# 555.net
KiCad netlist of a schematic drawn in Altium Designer
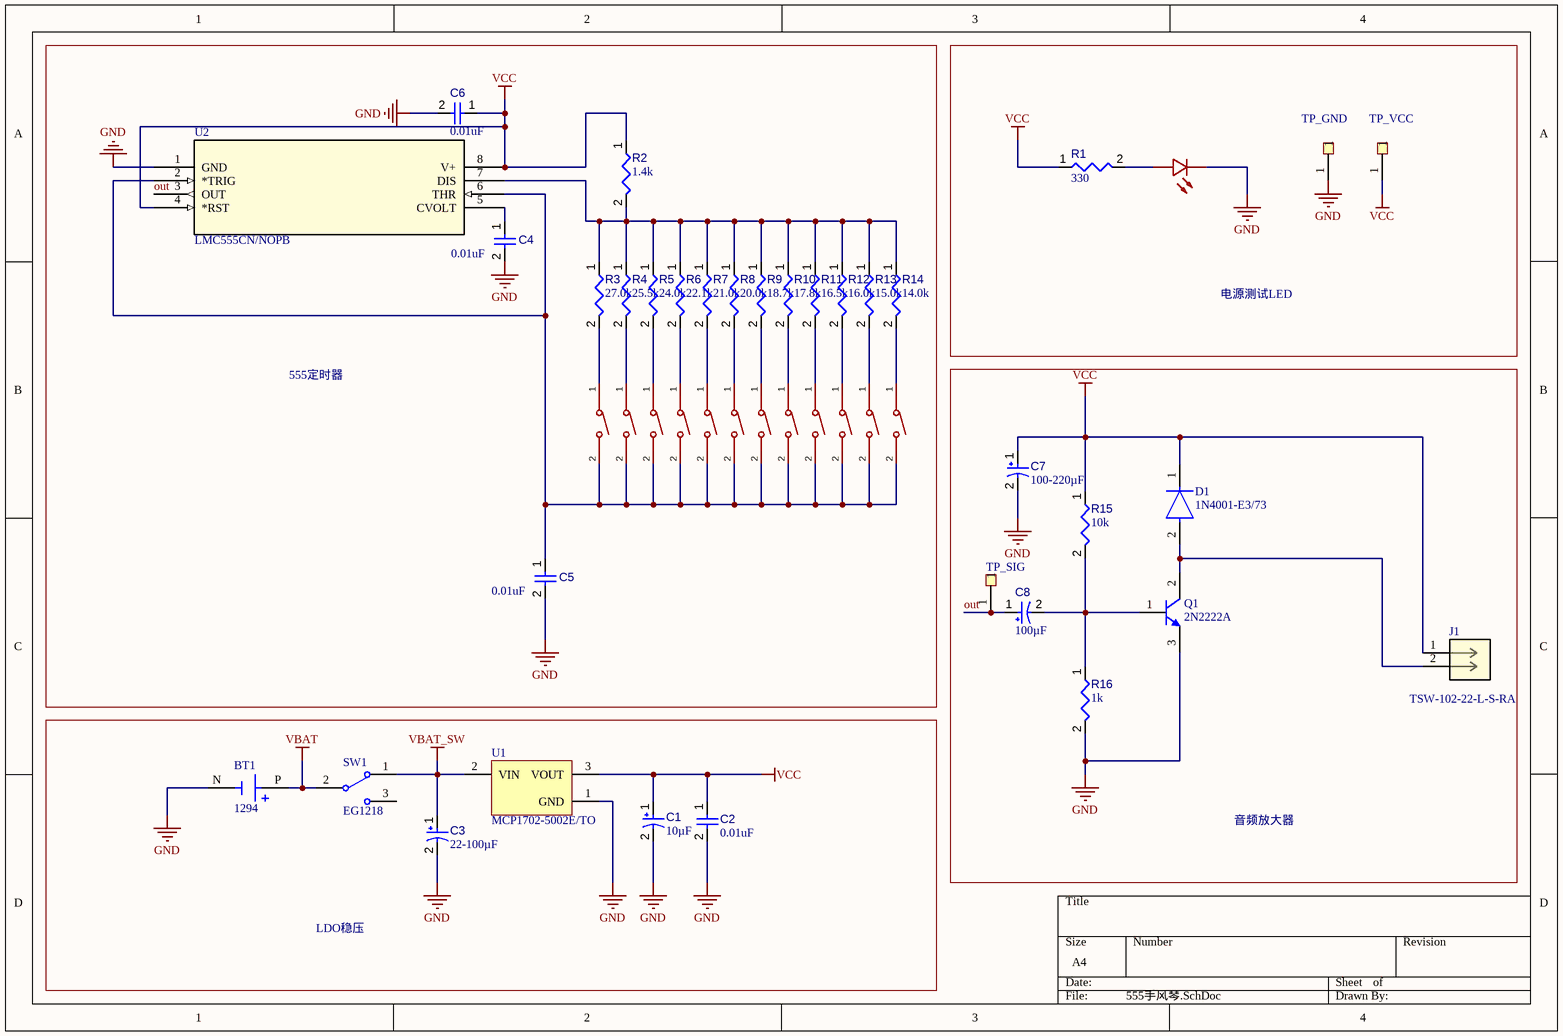
[diagram p0: 555手风琴.SchDoc]

(export (version "E")
  (design (tool "Eeschema 10.0.6"))
  (components
    (comp (ref "BT1")
      (value "1294")
      (footprint "BAT_1294")
      (description "9 Volt Battery Holder- PC Terminals")
      (fields (field (name "MF") "Keystone Electronics"))
      (libsource (lib "keystone1294电池底座") (part "1294"))
    )
    (comp (ref "C1")
      (value "10µF")
      (footprint "CAPMP3217X18-T_V")
      (description "Standard Tantalum, 10 uF, +/- 10%, 16 V, -55 to 125 degC, 1206 (3216 Metric), RoHS, Tape and Reel")
      (fields (field (name "TOLERANCE") "10%") (field (name "MANUFACTURER") "AVX"))
      (libsource (lib "") (part "CAP-P-2_1"))
    )
    (comp (ref "C2")
      (value "0.01uF")
      (footprint "CAPC2013X95X50LL10T25")
      (description "Chip Capacitor, 100 nF, +/- 10%, 50 V, 0805 (2012 Metric)")
      (fields (field (name "TOLERANCE") "10%") (field (name "Comment") "Capacitor 100 nF +/-10% 50 V 0805"))
      (libsource (lib "新宇 付") (part "CAP-NP-2"))
    )
    (comp (ref "C3")
      (value "22-100µF")
      (footprint "CAPMP3217X18-T_V")
      (description "Standard Tantalum, 10 uF, +/- 10%, 16 V, -55 to 125 degC, 1206 (3216 Metric), RoHS, Tape and Reel")
      (fields (field (name "TOLERANCE") "10%") (field (name "MANUFACTURER") "AVX"))
      (libsource (lib "") (part "CAP-P-2_1"))
    )
    (comp (ref "C4")
      (value "0.01uF")
      (footprint "CAPC2013X95X50LL10T25")
      (description "Chip Capacitor, 100 nF, +/- 10%, 50 V, 0805 (2012 Metric)")
      (fields (field (name "TOLERANCE") "10%") (field (name "Comment") "Capacitor 100 nF +/-10% 50 V 0805"))
      (libsource (lib "新宇 付") (part "CAP-NP-2"))
    )
    (comp (ref "C5")
      (value "0.01uF")
      (footprint "CAPC2013X95X50LL10T25")
      (description "Chip Capacitor, 100 nF, +/- 10%, 50 V, 0805 (2012 Metric)")
      (fields (field (name "TOLERANCE") "10%") (field (name "Comment") "Capacitor 100 nF +/-10% 50 V 0805"))
      (libsource (lib "新宇 付") (part "CAP-NP-2"))
    )
    (comp (ref "C6")
      (value "0.01uF")
      (footprint "CAPC2013X95X50LL10T25")
      (description "Chip Capacitor, 100 nF, +/- 10%, 50 V, 0805 (2012 Metric)")
      (fields (field (name "TOLERANCE") "10%") (field (name "Comment") "Capacitor 100 nF +/-10% 50 V 0805"))
      (libsource (lib "新宇 付") (part "CAP-NP-2"))
    )
    (comp (ref "C7")
      (value "100-220µF")
      (footprint "CAPMP3217X18-T_V")
      (description "Standard Tantalum, 10 uF, +/- 10%, 16 V, -55 to 125 degC, 1206 (3216 Metric), RoHS, Tape and Reel")
      (fields (field (name "TOLERANCE") "10%") (field (name "MANUFACTURER") "AVX"))
      (libsource (lib "") (part "CAP-P-2_1"))
    )
    (comp (ref "C8")
      (value "100µF")
      (footprint "CAPMP3217X18-T_V")
      (description "Standard Tantalum, 10 uF, +/- 10%, 16 V, -55 to 125 degC, 1206 (3216 Metric), RoHS, Tape and Reel")
      (fields (field (name "TOLERANCE") "10%") (field (name "MANUFACTURER") "AVX"))
      (libsource (lib "新宇 付") (part "CAP-P-2"))
    )
    (comp (ref "D1")
      (value "1N4001-E3/73")
      (footprint "FP-1N4001-E3-73-MFG")
      (description "DIODE GEN PURP 50V 1A DO204AL")
      (fields
        (field (name "MANUFACTURER") "Vishay")
        (field (name "OCTOPART") "https://octopart.com/1n4001-e3%2F73-vishay-42330130")
      )
      (libsource (lib "Altium Content Vault") (part "d7152d700b627762746794eb795d46e"))
    )
    (comp (ref "J1")
      (value "TSW-102-22-L-S-RA")
      (footprint "CON2_1X2_TR_TSW_SAI")
      (description "No Description Available")
      (fields (field (name "COPYRIGHT") "Copyright (C) 2026 Ultra Librarian. All rights reserved."))
      (libsource (lib "TSW-102-22-L-S-RA") (part "TSW-102-22-L-S-RA"))
    )
    (comp (ref "LED1")
      (value "FC-DA1608HRK-620D")
      (footprint "LED0603-RD_RED")
      (libsource (lib "C84263_发光二极管-LED_0603") (part "FC-DA1608HRK-620D"))
    )
    (comp (ref "Q1")
      (value "2N2222A")
      (footprint "STM-TO-18-3")
      (description "High Speed Switch, 0.6 A IC, -65 to 175 degC, 3-Pin TO-18, RoHS, Bulk")
      (fields (field (name "MANUFACTURER") "STMicroelectronics"))
      (libsource (lib "Altium Content Vault") (part "NPN_B1C2E3-3"))
    )
    (comp (ref "R1")
      (value "330")
      (footprint "RESC0402(1005)_L")
      (description "100R 0.063W 1% 0402 (1005 Metric)  SMD")
      (fields (field (name "TOLERANCE") "1%") (field (name "POWER") "63mW"))
      (libsource (lib "新宇 付") (part "100R2F"))
    )
    (comp (ref "R2")
      (value "1.4k")
      (footprint "RESC0402(1005)_L")
      (description "100R 0.063W 1% 0402 (1005 Metric)  SMD")
      (fields (field (name "TOLERANCE") "1%") (field (name "POWER") "63mW"))
      (libsource (lib "新宇 付") (part "100R2F"))
    )
    (comp (ref "R3")
      (value "27.0k")
      (footprint "RESC0402(1005)_L")
      (description "100R 0.063W 1% 0402 (1005 Metric)  SMD")
      (fields (field (name "TOLERANCE") "1%") (field (name "POWER") "63mW"))
      (libsource (lib "新宇 付") (part "100R2F"))
    )
    (comp (ref "R4")
      (value "25.5k")
      (footprint "RESC0402(1005)_L")
      (description "100R 0.063W 1% 0402 (1005 Metric)  SMD")
      (fields (field (name "TOLERANCE") "1%") (field (name "POWER") "63mW"))
      (libsource (lib "新宇 付") (part "100R2F"))
    )
    (comp (ref "R5")
      (value "24.0k")
      (footprint "RESC0402(1005)_L")
      (description "100R 0.063W 1% 0402 (1005 Metric)  SMD")
      (fields (field (name "TOLERANCE") "1%") (field (name "POWER") "63mW"))
      (libsource (lib "新宇 付") (part "100R2F"))
    )
    (comp (ref "R6")
      (value "22.1k")
      (footprint "RESC0402(1005)_L")
      (description "100R 0.063W 1% 0402 (1005 Metric)  SMD")
      (fields (field (name "TOLERANCE") "1%") (field (name "POWER") "63mW"))
      (libsource (lib "新宇 付") (part "100R2F"))
    )
    (comp (ref "R7")
      (value "21.0k")
      (footprint "RESC0402(1005)_L")
      (description "100R 0.063W 1% 0402 (1005 Metric)  SMD")
      (fields (field (name "TOLERANCE") "1%") (field (name "POWER") "63mW"))
      (libsource (lib "新宇 付") (part "100R2F"))
    )
    (comp (ref "R8")
      (value "20.0k")
      (footprint "RESC0402(1005)_L")
      (description "100R 0.063W 1% 0402 (1005 Metric)  SMD")
      (fields (field (name "TOLERANCE") "1%") (field (name "POWER") "63mW"))
      (libsource (lib "新宇 付") (part "100R2F"))
    )
    (comp (ref "R9")
      (value "18.7k")
      (footprint "RESC0402(1005)_L")
      (description "100R 0.063W 1% 0402 (1005 Metric)  SMD")
      (fields (field (name "TOLERANCE") "1%") (field (name "POWER") "63mW"))
      (libsource (lib "新宇 付") (part "100R2F"))
    )
    (comp (ref "R10")
      (value "17.8k")
      (footprint "RESC0402(1005)_L")
      (description "100R 0.063W 1% 0402 (1005 Metric)  SMD")
      (fields (field (name "TOLERANCE") "1%") (field (name "POWER") "63mW"))
      (libsource (lib "新宇 付") (part "100R2F"))
    )
    (comp (ref "R11")
      (value "16.5k")
      (footprint "RESC0402(1005)_L")
      (description "100R 0.063W 1% 0402 (1005 Metric)  SMD")
      (fields (field (name "TOLERANCE") "1%") (field (name "POWER") "63mW"))
      (libsource (lib "新宇 付") (part "100R2F"))
    )
    (comp (ref "R12")
      (value "16.0k")
      (footprint "RESC0402(1005)_L")
      (description "100R 0.063W 1% 0402 (1005 Metric)  SMD")
      (fields (field (name "TOLERANCE") "1%") (field (name "POWER") "63mW"))
      (libsource (lib "新宇 付") (part "100R2F"))
    )
    (comp (ref "R13")
      (value "15.0k")
      (footprint "RESC0402(1005)_L")
      (description "100R 0.063W 1% 0402 (1005 Metric)  SMD")
      (fields (field (name "TOLERANCE") "1%") (field (name "POWER") "63mW"))
      (libsource (lib "新宇 付") (part "100R2F"))
    )
    (comp (ref "R14")
      (value "14.0k")
      (footprint "RESC0402(1005)_L")
      (description "100R 0.063W 1% 0402 (1005 Metric)  SMD")
      (fields (field (name "TOLERANCE") "1%") (field (name "POWER") "63mW"))
      (libsource (lib "新宇 付") (part "100R2F"))
    )
    (comp (ref "R15")
      (value "10k")
      (footprint "RESC0402(1005)_L")
      (description "100R 0.063W 1% 0402 (1005 Metric)  SMD")
      (fields (field (name "TOLERANCE") "1%") (field (name "POWER") "63mW"))
      (libsource (lib "新宇 付") (part "100R2F"))
    )
    (comp (ref "R16")
      (value "1k")
      (footprint "RESC0402(1005)_L")
      (description "100R 0.063W 1% 0402 (1005 Metric)  SMD")
      (fields (field (name "TOLERANCE") "1%") (field (name "POWER") "63mW"))
      (libsource (lib "新宇 付") (part "100R2F"))
    )
    (comp (ref "SW1")
      (value "EG1218")
      (footprint "ESWI-EG1218_V")
      (description "Slide Switch, 500 V, -20 to 70 degC, 3-Pin THD, RoHS")
      (libsource (lib "EG1218单刀双掷滑动开关") (part "CMP-1696-00002-1"))
    )
    (comp (ref "SW2")
      (value "TS-1088-AR02016")
      (footprint "SW-SMD_L3.9-W3.0-P4.45")
      (libsource (lib "Click_switch") (part "TS-1088-AR02016"))
    )
    (comp (ref "SW3")
      (value "TS-1088-AR02016")
      (footprint "SW-SMD_L3.9-W3.0-P4.45")
      (libsource (lib "Click_switch") (part "TS-1088-AR02016"))
    )
    (comp (ref "SW4")
      (value "TS-1088-AR02016")
      (footprint "SW-SMD_L3.9-W3.0-P4.45")
      (libsource (lib "Click_switch") (part "TS-1088-AR02016"))
    )
    (comp (ref "SW5")
      (value "TS-1088-AR02016")
      (footprint "SW-SMD_L3.9-W3.0-P4.45")
      (libsource (lib "Click_switch") (part "TS-1088-AR02016"))
    )
    (comp (ref "SW6")
      (value "TS-1088-AR02016")
      (footprint "SW-SMD_L3.9-W3.0-P4.45")
      (libsource (lib "Click_switch") (part "TS-1088-AR02016"))
    )
    (comp (ref "SW7")
      (value "TS-1088-AR02016")
      (footprint "SW-SMD_L3.9-W3.0-P4.45")
      (libsource (lib "Click_switch") (part "TS-1088-AR02016"))
    )
    (comp (ref "SW8")
      (value "TS-1088-AR02016")
      (footprint "SW-SMD_L3.9-W3.0-P4.45")
      (libsource (lib "Click_switch") (part "TS-1088-AR02016"))
    )
    (comp (ref "SW9")
      (value "TS-1088-AR02016")
      (footprint "SW-SMD_L3.9-W3.0-P4.45")
      (libsource (lib "Click_switch") (part "TS-1088-AR02016"))
    )
    (comp (ref "SW10")
      (value "TS-1088-AR02016")
      (footprint "SW-SMD_L3.9-W3.0-P4.45")
      (libsource (lib "Click_switch") (part "TS-1088-AR02016"))
    )
    (comp (ref "SW11")
      (value "TS-1088-AR02016")
      (footprint "SW-SMD_L3.9-W3.0-P4.45")
      (libsource (lib "Click_switch") (part "TS-1088-AR02016"))
    )
    (comp (ref "SW12")
      (value "TS-1088-AR02016")
      (footprint "SW-SMD_L3.9-W3.0-P4.45")
      (libsource (lib "Click_switch") (part "TS-1088-AR02016"))
    )
    (comp (ref "SW13")
      (value "TS-1088-AR02016")
      (footprint "SW-SMD_L3.9-W3.0-P4.45")
      (libsource (lib "Click_switch") (part "TS-1088-AR02016"))
    )
    (comp (ref "TP_GND")
      (value "Component_1")
      (footprint "PCBComponent_1")
      (libsource (lib "testpoint") (part "Component_1"))
    )
    (comp (ref "TP_SIG")
      (value "Component_1")
      (footprint "PCBComponent_1")
      (libsource (lib "testpoint") (part "Component_1"))
    )
    (comp (ref "TP_VCC")
      (value "Component_1")
      (footprint "PCBComponent_1")
      (libsource (lib "testpoint") (part "Component_1"))
    )
    (comp (ref "U1")
      (value "MCP1702-5002E/TO")
      (footprint "TO-92-TO3")
      (description "250 mA Low Quiescent Current LDO Regulator, 3-Pin TO-92, Extended TemperatureBAG")
      (libsource (lib "Altium Content Vault") (part "PM-LINEREG-MCP1702-IL3A"))
    )
    (comp (ref "U2")
      (value "LMC555CN/NOPB")
      (footprint "N08E_TEX")
      (description "Worldâ€™s smallest 555 timer with low power, high accuracy and a Fmax of 3MHz 8-PDIP -40 to 85")
      (fields (field (name "COPYRIGHT") "Copyright (C) 2025 Ultra Librarian. All rights reserved."))
      (libsource (lib "LMC555CNNOPB") (part "LMC555CNNOPB"))
    )
  )
  (nets
    (net (code "1") (name "/out") (class "Default")
      (node (ref "C8") (pin "1") (pinfunction "1_1") (pintype "passive"))
      (node (ref "TP_SIG") (pin "1") (pinfunction "1_1") (pintype "passive"))
      (node (ref "U2") (pin "3") (pinfunction "OUT_3") (pintype "output"))
    )
    (net (code "2") (name "GND") (class "Default")
      (node (ref "BT1") (pin "N") (pinfunction "NEG_N") (pintype "passive"))
      (node (ref "C1") (pin "2") (pinfunction "2_2") (pintype "passive"))
      (node (ref "C2") (pin "2") (pinfunction "2_2") (pintype "passive"))
      (node (ref "C3") (pin "2") (pinfunction "2_2") (pintype "passive"))
      (node (ref "C4") (pin "2") (pinfunction "2_2") (pintype "passive"))
      (node (ref "C5") (pin "2") (pinfunction "2_2") (pintype "passive"))
      (node (ref "C6") (pin "2") (pinfunction "2_2") (pintype "passive"))
      (node (ref "C7") (pin "2") (pinfunction "2_2") (pintype "passive"))
      (node (ref "LED1") (pin "1") (pinfunction "K_1") (pintype "passive"))
      (node (ref "Q1") (pin "3") (pinfunction "E_3") (pintype "passive"))
      (node (ref "R16") (pin "2") (pinfunction "2_2") (pintype "passive"))
      (node (ref "TP_GND") (pin "1") (pinfunction "1_1") (pintype "passive"))
      (node (ref "U1") (pin "1") (pinfunction "GND_1") (pintype "power_in"))
      (node (ref "U2") (pin "1") (pinfunction "GND_1") (pintype "power_in"))
    )
    (net (code "3") (name "Net-(D1-A)") (class "Default")
      (node (ref "D1") (pin "2") (pinfunction "A_2") (pintype "passive"))
      (node (ref "J1") (pin "2") (pinfunction "2_2") (pintype "passive"))
      (node (ref "Q1") (pin "2") (pinfunction "C_2") (pintype "passive"))
    )
    (net (code "4") (name "Net-(LED1-A)") (class "Default")
      (node (ref "LED1") (pin "2") (pinfunction "A_2") (pintype "passive"))
      (node (ref "R1") (pin "2") (pinfunction "2_2") (pintype "passive"))
    )
    (net (code "5") (name "Net-(Q1-B)") (class "Default")
      (node (ref "C8") (pin "2") (pinfunction "2_2") (pintype "passive"))
      (node (ref "Q1") (pin "1") (pinfunction "B_1") (pintype "passive"))
      (node (ref "R15") (pin "2") (pinfunction "2_2") (pintype "passive"))
      (node (ref "R16") (pin "1") (pinfunction "1_1") (pintype "passive"))
    )
    (net (code "6") (name "Net-(R3-Pad2)") (class "Default")
      (node (ref "R3") (pin "2") (pinfunction "2_2") (pintype "passive"))
      (node (ref "SW2") (pin "1") (pinfunction "1_1") (pintype "passive"))
    )
    (net (code "7") (name "Net-(R4-Pad2)") (class "Default")
      (node (ref "R4") (pin "2") (pinfunction "2_2") (pintype "passive"))
      (node (ref "SW3") (pin "1") (pinfunction "1_1") (pintype "passive"))
    )
    (net (code "8") (name "Net-(R5-Pad2)") (class "Default")
      (node (ref "R5") (pin "2") (pinfunction "2_2") (pintype "passive"))
      (node (ref "SW4") (pin "1") (pinfunction "1_1") (pintype "passive"))
    )
    (net (code "9") (name "Net-(R6-Pad2)") (class "Default")
      (node (ref "R6") (pin "2") (pinfunction "2_2") (pintype "passive"))
      (node (ref "SW5") (pin "1") (pinfunction "1_1") (pintype "passive"))
    )
    (net (code "10") (name "Net-(R7-Pad2)") (class "Default")
      (node (ref "R7") (pin "2") (pinfunction "2_2") (pintype "passive"))
      (node (ref "SW6") (pin "1") (pinfunction "1_1") (pintype "passive"))
    )
    (net (code "11") (name "Net-(R8-Pad2)") (class "Default")
      (node (ref "R8") (pin "2") (pinfunction "2_2") (pintype "passive"))
      (node (ref "SW7") (pin "1") (pinfunction "1_1") (pintype "passive"))
    )
    (net (code "12") (name "Net-(R9-Pad2)") (class "Default")
      (node (ref "R9") (pin "2") (pinfunction "2_2") (pintype "passive"))
      (node (ref "SW8") (pin "1") (pinfunction "1_1") (pintype "passive"))
    )
    (net (code "13") (name "Net-(R10-Pad2)") (class "Default")
      (node (ref "R10") (pin "2") (pinfunction "2_2") (pintype "passive"))
      (node (ref "SW9") (pin "1") (pinfunction "1_1") (pintype "passive"))
    )
    (net (code "14") (name "Net-(R11-Pad2)") (class "Default")
      (node (ref "R11") (pin "2") (pinfunction "2_2") (pintype "passive"))
      (node (ref "SW10") (pin "1") (pinfunction "1_1") (pintype "passive"))
    )
    (net (code "15") (name "Net-(R12-Pad2)") (class "Default")
      (node (ref "R12") (pin "2") (pinfunction "2_2") (pintype "passive"))
      (node (ref "SW11") (pin "1") (pinfunction "1_1") (pintype "passive"))
    )
    (net (code "16") (name "Net-(R13-Pad2)") (class "Default")
      (node (ref "R13") (pin "2") (pinfunction "2_2") (pintype "passive"))
      (node (ref "SW12") (pin "1") (pinfunction "1_1") (pintype "passive"))
    )
    (net (code "17") (name "Net-(R14-Pad2)") (class "Default")
      (node (ref "R14") (pin "2") (pinfunction "2_2") (pintype "passive"))
      (node (ref "SW13") (pin "1") (pinfunction "1_1") (pintype "passive"))
    )
    (net (code "18") (name "Net-(U2-*TRIG)") (class "Default")
      (node (ref "C5") (pin "1") (pinfunction "1_1") (pintype "passive"))
      (node (ref "SW10") (pin "2") (pinfunction "2_2") (pintype "passive"))
      (node (ref "SW11") (pin "2") (pinfunction "2_2") (pintype "passive"))
      (node (ref "SW12") (pin "2") (pinfunction "2_2") (pintype "passive"))
      (node (ref "SW13") (pin "2") (pinfunction "2_2") (pintype "passive"))
      (node (ref "SW2") (pin "2") (pinfunction "2_2") (pintype "passive"))
      (node (ref "SW3") (pin "2") (pinfunction "2_2") (pintype "passive"))
      (node (ref "SW4") (pin "2") (pinfunction "2_2") (pintype "passive"))
      (node (ref "SW5") (pin "2") (pinfunction "2_2") (pintype "passive"))
      (node (ref "SW6") (pin "2") (pinfunction "2_2") (pintype "passive"))
      (node (ref "SW7") (pin "2") (pinfunction "2_2") (pintype "passive"))
      (node (ref "SW8") (pin "2") (pinfunction "2_2") (pintype "passive"))
      (node (ref "SW9") (pin "2") (pinfunction "2_2") (pintype "passive"))
      (node (ref "U2") (pin "2") (pinfunction "*TRIG_2") (pintype "input"))
      (node (ref "U2") (pin "6") (pinfunction "THR_6") (pintype "input"))
    )
    (net (code "19") (name "Net-(U2-CVOLT)") (class "Default")
      (node (ref "C4") (pin "1") (pinfunction "1_1") (pintype "passive"))
      (node (ref "U2") (pin "5") (pinfunction "CVOLT_5") (pintype "passive"))
    )
    (net (code "20") (name "Net-(U2-DIS)") (class "Default")
      (node (ref "R10") (pin "1") (pinfunction "1_1") (pintype "passive"))
      (node (ref "R11") (pin "1") (pinfunction "1_1") (pintype "passive"))
      (node (ref "R12") (pin "1") (pinfunction "1_1") (pintype "passive"))
      (node (ref "R13") (pin "1") (pinfunction "1_1") (pintype "passive"))
      (node (ref "R14") (pin "1") (pinfunction "1_1") (pintype "passive"))
      (node (ref "R2") (pin "2") (pinfunction "2_2") (pintype "passive"))
      (node (ref "R3") (pin "1") (pinfunction "1_1") (pintype "passive"))
      (node (ref "R4") (pin "1") (pinfunction "1_1") (pintype "passive"))
      (node (ref "R5") (pin "1") (pinfunction "1_1") (pintype "passive"))
      (node (ref "R6") (pin "1") (pinfunction "1_1") (pintype "passive"))
      (node (ref "R7") (pin "1") (pinfunction "1_1") (pintype "passive"))
      (node (ref "R8") (pin "1") (pinfunction "1_1") (pintype "passive"))
      (node (ref "R9") (pin "1") (pinfunction "1_1") (pintype "passive"))
      (node (ref "U2") (pin "7") (pinfunction "DIS_7") (pintype "passive"))
    )
    (net (code "21") (name "VBAT") (class "Default")
      (node (ref "BT1") (pin "P") (pinfunction "POS_P") (pintype "passive"))
      (node (ref "SW1") (pin "2") (pinfunction "COM_2") (pintype "passive"))
    )
    (net (code "22") (name "VBAT_SW") (class "Default")
      (node (ref "C3") (pin "1") (pinfunction "1_1") (pintype "passive"))
      (node (ref "SW1") (pin "1") (pinfunction "1_1") (pintype "passive"))
      (node (ref "U1") (pin "2") (pinfunction "VIN_2") (pintype "power_in"))
    )
    (net (code "23") (name "VCC") (class "Default")
      (node (ref "C1") (pin "1") (pinfunction "1_1") (pintype "passive"))
      (node (ref "C2") (pin "1") (pinfunction "1_1") (pintype "passive"))
      (node (ref "C6") (pin "1") (pinfunction "1_1") (pintype "passive"))
      (node (ref "C7") (pin "1") (pinfunction "1_1") (pintype "passive"))
      (node (ref "D1") (pin "1") (pinfunction "C_1") (pintype "passive"))
      (node (ref "J1") (pin "1") (pinfunction "1_1") (pintype "passive"))
      (node (ref "R1") (pin "1") (pinfunction "1_1") (pintype "passive"))
      (node (ref "R15") (pin "1") (pinfunction "1_1") (pintype "passive"))
      (node (ref "R2") (pin "1") (pinfunction "1_1") (pintype "passive"))
      (node (ref "TP_VCC") (pin "1") (pinfunction "1_1") (pintype "passive"))
      (node (ref "U1") (pin "3") (pinfunction "VOUT_3") (pintype "power_in"))
      (node (ref "U2") (pin "4") (pinfunction "*RST_4") (pintype "input"))
      (node (ref "U2") (pin "8") (pinfunction "V+_8") (pintype "power_in"))
    )
    (net (code "24") (name "unconnected-(SW1-Pad3)") (class "Default")
      (node (ref "SW1") (pin "3") (pinfunction "3_3") (pintype "passive"))
    )
  )
)
